# IOT_Gas.net
KiCad netlist of a schematic drawn in Altium Designer
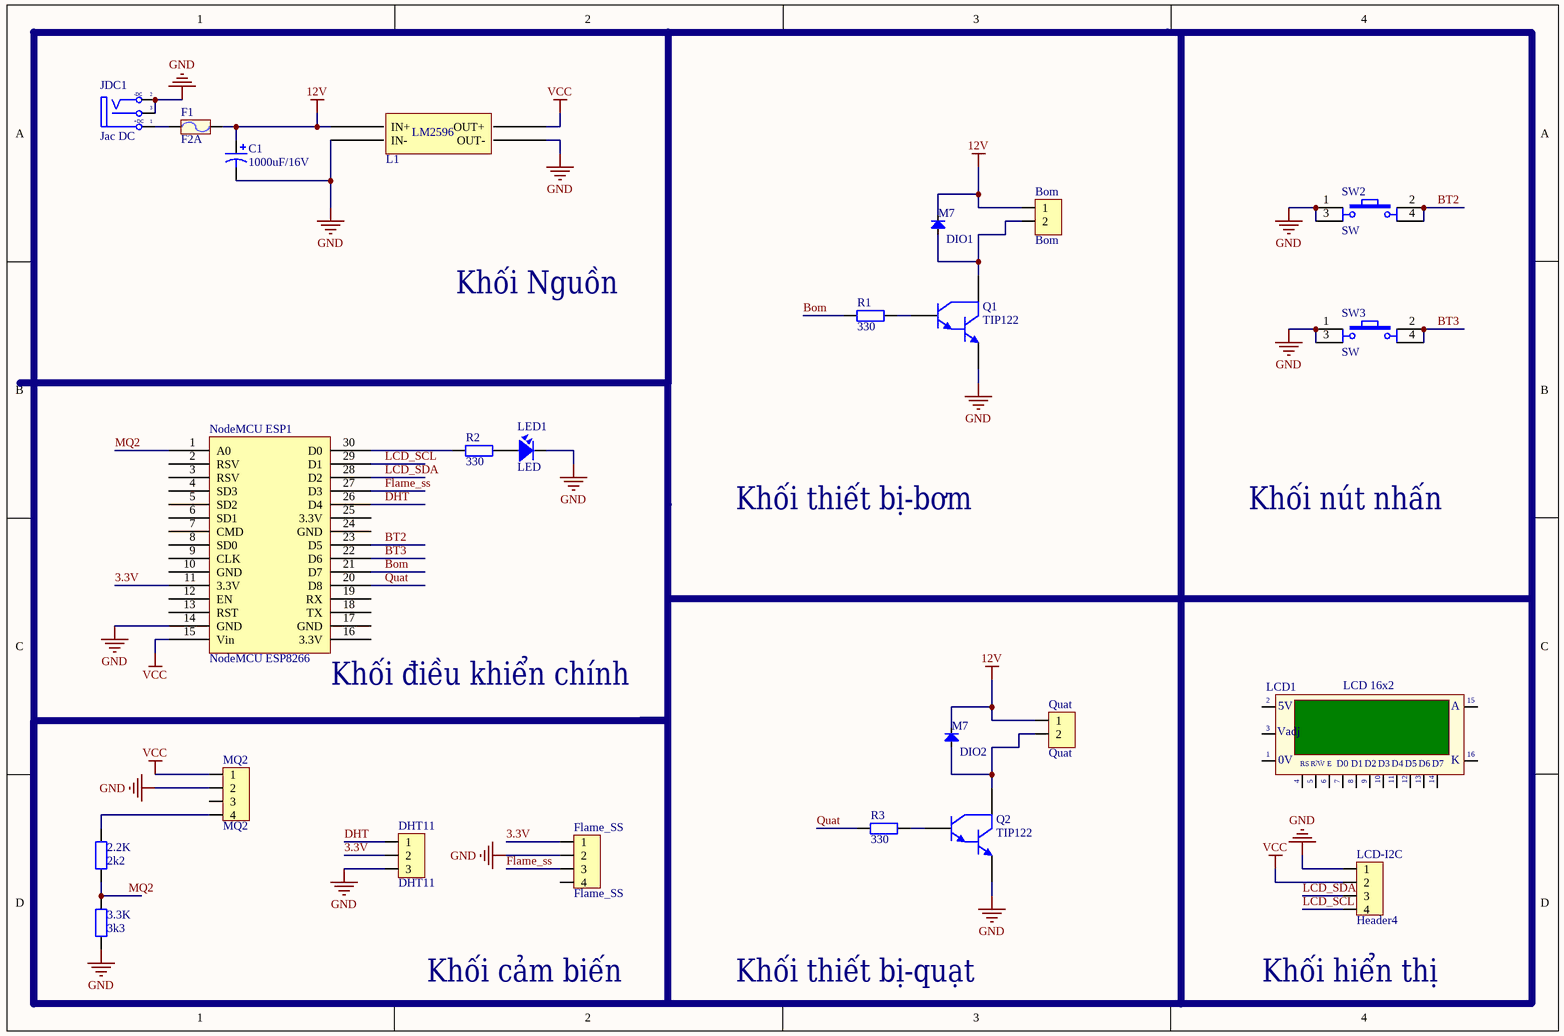
[diagram p0: IOT_Gas.SchDoc]

(export (version "E")
  (design (tool "Eeschema 10.0.6"))
  (components
    (comp (ref "2.2K")
      (value "2k2")
      (footprint "DIEN TRO 0805")
      (description "Resistor SMD 0805")
      (fields (field (name "PUBLISHER") "Altium Limited"))
      (libsource (lib "") (part "R0805_1"))
    )
    (comp (ref "3.3K")
      (value "3k3")
      (footprint "DIEN TRO 0805")
      (description "Resistor SMD 0805")
      (fields (field (name "PUBLISHER") "Altium Limited"))
      (libsource (lib "") (part "R0805_1"))
    )
    (comp (ref "Bom")
      (value "Bom")
      (footprint "Header2")
      (description "Header IDC, 2 x 1 Pin Vertical 2.54mm Pitch (Non-Boxed, Male)")
      (fields
        (field (name "MANUFACTURER") "Würth Elektronik eiSos GmbH")
        (field (name "PARTNO") "613002143121")
        (field (name "CREATED BY") "Karrer Zheng")
      )
      (libsource (lib "My Library") (part "Header2"))
    )
    (comp (ref "C1")
      (value "1000uF/16V")
      (footprint "C10mm")
      (description "Polarized Capacitor (Axial)")
      (fields (field (name "PUBLISHER") "Altium Limited"))
      (libsource (lib "My Library") (part "Cap Pol 12mm"))
    )
    (comp (ref "DHT11")
      (value "DHT11")
      (footprint "Header3")
      (description "Header IDC, 3 x 1 Pin Vertical 2.54mm Pitch (Non-Boxed, Male)")
      (fields
        (field (name "MANUFACTURER") "Würth Elektronik eiSos GmbH")
        (field (name "PARTNO") "613002143121")
        (field (name "CREATED BY") "Karrer Zheng")
      )
      (libsource (lib "My Library") (part "Header3"))
    )
    (comp (ref "DIO1")
      (value "M7")
      (footprint "DIO-SMD-106")
      (description "Default Diode")
      (fields (field (name "PUBLISHER") "Altium Limited"))
      (libsource (lib "My Library (1)") (part "Diode SMD"))
    )
    (comp (ref "DIO2")
      (value "M7")
      (footprint "DIO-SMD-106")
      (description "Default Diode")
      (fields (field (name "PUBLISHER") "Altium Limited"))
      (libsource (lib "My Library (1)") (part "Diode SMD"))
    )
    (comp (ref "F1")
      (value "F2A")
      (footprint "Fuse")
      (description "Fuse")
      (fields (field (name "DESIGNED BY") "VanDungEvn"))
      (libsource (lib "My Library") (part "Fuse"))
    )
    (comp (ref "Flame_SS")
      (value "Flame_SS")
      (footprint "HDR4")
      (description "Header IDC, 4 x 1 Pin Vertical 2.54mm Pitch (Non-Boxed, Male)")
      (fields
        (field (name "MANUFACTURER") "Würth Elektronik eiSos GmbH")
        (field (name "PARTNO") "613002143121")
        (field (name "CREATED BY") "Karrer Zheng")
      )
      (libsource (lib "My Library") (part "Header4"))
    )
    (comp (ref "JDC1")
      (value "Jac DC")
      (footprint "DC-IN")
      (description "Jac DC input")
      (libsource (lib "My Library") (part "DCIN"))
    )
    (comp (ref "L1")
      (value "BUCK_LM2596")
      (footprint "BUCK_LM2596")
      (libsource (lib "BUCK_LM2596_Sch") (part "BUCK_LM2596"))
    )
    (comp (ref "LCD-I2C")
      (value "Header4")
      (footprint "HDR4")
      (description "Header IDC, 4 x 1 Pin Vertical 2.54mm Pitch (Non-Boxed, Male)")
      (fields
        (field (name "MANUFACTURER") "Würth Elektronik eiSos GmbH")
        (field (name "PARTNO") "613002143121")
        (field (name "CREATED BY") "Karrer Zheng")
      )
      (libsource (lib "My Library") (part "Header4"))
    )
    (comp (ref "LCD1")
      (value "LCD 16x2")
      (footprint "LCD16X2N")
      (libsource (lib "My library altium") (part "LCD"))
    )
    (comp (ref "LED1")
      (value "LED")
      (footprint "LED-5 GRe")
      (description "LED Single colour Green and Red")
      (libsource (lib "My Library") (part "LED"))
    )
    (comp (ref "MQ2")
      (value "MQ2")
      (footprint "HDR4")
      (description "Header IDC, 4 x 1 Pin Vertical 2.54mm Pitch (Non-Boxed, Male)")
      (fields
        (field (name "MANUFACTURER") "Würth Elektronik eiSos GmbH")
        (field (name "PARTNO") "613002143121")
        (field (name "CREATED BY") "Karrer Zheng")
      )
      (libsource (lib "My Library") (part "Header4"))
    )
    (comp (ref "NodeMCU ESP1")
      (value "NodeMCU ESP8266")
      (footprint "NodeMCU ESP8266")
      (libsource (lib "Phieu_Du") (part "NodeMCU ESP8266"))
    )
    (comp (ref "Q1")
      (value "TIP122")
      (footprint "QTO-220")
      (description "Darlington Silicon Power NPN Transistor, 8 Amp, 100 Volts and 65 Watts")
      (libsource (lib "My Library (1)") (part "TIP122"))
    )
    (comp (ref "Q2")
      (value "TIP122")
      (footprint "QTO-220")
      (description "Darlington Silicon Power NPN Transistor, 8 Amp, 100 Volts and 65 Watts")
      (libsource (lib "My Library (1)") (part "TIP122"))
    )
    (comp (ref "Quat")
      (value "Quat")
      (footprint "Header2")
      (description "Header IDC, 2 x 1 Pin Vertical 2.54mm Pitch (Non-Boxed, Male)")
      (fields
        (field (name "MANUFACTURER") "Würth Elektronik eiSos GmbH")
        (field (name "PARTNO") "613002143121")
        (field (name "CREATED BY") "Karrer Zheng")
      )
      (libsource (lib "My Library") (part "Header2"))
    )
    (comp (ref "R1")
      (value "330")
      (footprint "DIEN TRO 0805")
      (description "Resistor SMD 0805")
      (fields (field (name "PUBLISHER") "Altium Limited"))
      (libsource (lib "My Library (1)") (part "R0805"))
    )
    (comp (ref "R2")
      (value "330")
      (footprint "DIEN TRO 0805")
      (description "Resistor SMD 0805")
      (fields (field (name "PUBLISHER") "Altium Limited"))
      (libsource (lib "My Library (1)") (part "R0805"))
    )
    (comp (ref "R3")
      (value "330")
      (footprint "DIEN TRO 0805")
      (description "Resistor SMD 0805")
      (fields (field (name "PUBLISHER") "Altium Limited"))
      (libsource (lib "My Library (1)") (part "R0805"))
    )
    (comp (ref "SW2")
      (value "SW")
      (footprint "SW4")
      (description "Switch button 4 pin")
      (libsource (lib "My Library (1)") (part "SW4"))
    )
    (comp (ref "SW3")
      (value "SW")
      (footprint "SW4")
      (description "Switch button 4 pin")
      (libsource (lib "My Library (1)") (part "SW4"))
    )
  )
  (nets
    (net (code "1") (name "/3.3V") (class "Default")
      (node (ref "DHT11") (pin "2") (pinfunction "2_2") (pintype "passive"))
      (node (ref "Flame_SS") (pin "1") (pinfunction "1_1") (pintype "passive"))
      (node (ref "NodeMCU ESP1") (pin "11") (pinfunction "3.3V_11") (pintype "passive"))
    )
    (net (code "2") (name "/BT2") (class "Default")
      (node (ref "NodeMCU ESP1") (pin "23") (pinfunction "D5_23") (pintype "passive"))
      (node (ref "SW2") (pin "2") (pintype "passive"))
      (node (ref "SW2") (pin "4") (pintype "passive"))
    )
    (net (code "3") (name "/BT3") (class "Default")
      (node (ref "NodeMCU ESP1") (pin "22") (pinfunction "D6_22") (pintype "passive"))
      (node (ref "SW3") (pin "2") (pintype "passive"))
      (node (ref "SW3") (pin "4") (pintype "passive"))
    )
    (net (code "4") (name "/Bom") (class "Default")
      (node (ref "NodeMCU ESP1") (pin "21") (pinfunction "D7_21") (pintype "passive"))
      (node (ref "R1") (pin "2") (pinfunction "2_2") (pintype "passive"))
    )
    (net (code "5") (name "/DHT") (class "Default")
      (node (ref "DHT11") (pin "1") (pinfunction "1_1") (pintype "passive"))
      (node (ref "NodeMCU ESP1") (pin "26") (pinfunction "D4_26") (pintype "passive"))
    )
    (net (code "6") (name "/Flame_ss") (class "Default")
      (node (ref "Flame_SS") (pin "3") (pinfunction "3_3") (pintype "passive"))
      (node (ref "NodeMCU ESP1") (pin "27") (pinfunction "D3_27") (pintype "passive"))
    )
    (net (code "7") (name "/LCD_SCL") (class "Default")
      (node (ref "LCD-I2C") (pin "4") (pinfunction "4_4") (pintype "passive"))
      (node (ref "NodeMCU ESP1") (pin "29") (pinfunction "D1_29") (pintype "passive"))
    )
    (net (code "8") (name "/LCD_SDA") (class "Default")
      (node (ref "LCD-I2C") (pin "3") (pinfunction "3_3") (pintype "passive"))
      (node (ref "NodeMCU ESP1") (pin "28") (pinfunction "D2_28") (pintype "passive"))
    )
    (net (code "9") (name "/MQ2") (class "Default")
      (node (ref "2.2K") (pin "2") (pinfunction "2_2") (pintype "passive"))
      (node (ref "3.3K") (pin "1") (pinfunction "1_1") (pintype "passive"))
      (node (ref "NodeMCU ESP1") (pin "1") (pinfunction "A0_1") (pintype "passive"))
    )
    (net (code "10") (name "/Quat") (class "Default")
      (node (ref "NodeMCU ESP1") (pin "20") (pinfunction "D8_20") (pintype "passive"))
      (node (ref "R3") (pin "2") (pinfunction "2_2") (pintype "passive"))
    )
    (net (code "11") (name "12V") (class "Default")
      (node (ref "Bom") (pin "1") (pinfunction "1_1") (pintype "passive"))
      (node (ref "C1") (pin "1") (pinfunction "1_1") (pintype "passive"))
      (node (ref "DIO1") (pin "2") (pinfunction "K_2") (pintype "passive"))
      (node (ref "DIO2") (pin "2") (pinfunction "K_2") (pintype "passive"))
      (node (ref "F1") (pin "2") (pinfunction "2_2") (pintype "passive"))
      (node (ref "L1") (pin "1") (pinfunction "IN+_1") (pintype "passive"))
      (node (ref "Quat") (pin "1") (pinfunction "1_1") (pintype "passive"))
    )
    (net (code "12") (name "GND") (class "Default")
      (node (ref "3.3K") (pin "2") (pinfunction "2_2") (pintype "passive"))
      (node (ref "C1") (pin "2") (pinfunction "2_2") (pintype "passive"))
      (node (ref "DHT11") (pin "3") (pinfunction "3_3") (pintype "passive"))
      (node (ref "Flame_SS") (pin "2") (pinfunction "2_2") (pintype "passive"))
      (node (ref "JDC1") (pin "2") (pinfunction "TN_2") (pintype "passive"))
      (node (ref "JDC1") (pin "3") (pinfunction "S_3") (pintype "power_in"))
      (node (ref "L1") (pin "2") (pinfunction "IN-_2") (pintype "passive"))
      (node (ref "L1") (pin "3") (pinfunction "OUT-_3") (pintype "passive"))
      (node (ref "LCD-I2C") (pin "1") (pinfunction "1_1") (pintype "passive"))
      (node (ref "LED1") (pin "2") (pinfunction "2_2") (pintype "passive"))
      (node (ref "MQ2") (pin "2") (pinfunction "2_2") (pintype "passive"))
      (node (ref "NodeMCU ESP1") (pin "14") (pinfunction "GND_14") (pintype "passive"))
      (node (ref "Q1") (pin "3") (pinfunction "E_3") (pintype "passive"))
      (node (ref "Q2") (pin "3") (pinfunction "E_3") (pintype "passive"))
      (node (ref "SW2") (pin "1") (pintype "passive"))
      (node (ref "SW2") (pin "3") (pintype "passive"))
      (node (ref "SW3") (pin "1") (pintype "passive"))
      (node (ref "SW3") (pin "3") (pintype "passive"))
    )
    (net (code "13") (name "Net-(2.2K-Pad1)") (class "Default")
      (node (ref "2.2K") (pin "1") (pinfunction "1_1") (pintype "passive"))
      (node (ref "MQ2") (pin "4") (pinfunction "4_4") (pintype "passive"))
    )
    (net (code "14") (name "Net-(DIO1-A)") (class "Default")
      (node (ref "Bom") (pin "2") (pinfunction "2_2") (pintype "passive"))
      (node (ref "DIO1") (pin "1") (pinfunction "A_1") (pintype "passive"))
      (node (ref "Q1") (pin "2") (pinfunction "C_2") (pintype "passive"))
    )
    (net (code "15") (name "Net-(DIO2-A)") (class "Default")
      (node (ref "DIO2") (pin "1") (pinfunction "A_1") (pintype "passive"))
      (node (ref "Q2") (pin "2") (pinfunction "C_2") (pintype "passive"))
      (node (ref "Quat") (pin "2") (pinfunction "2_2") (pintype "passive"))
    )
    (net (code "16") (name "Net-(JDC1-T)") (class "Default")
      (node (ref "F1") (pin "1") (pinfunction "1_1") (pintype "passive"))
      (node (ref "JDC1") (pin "1") (pinfunction "T_1") (pintype "passive"))
    )
    (net (code "17") (name "Net-(LED1-Pad1)") (class "Default")
      (node (ref "LED1") (pin "1") (pinfunction "1_1") (pintype "passive"))
      (node (ref "R2") (pin "1") (pinfunction "1_1") (pintype "passive"))
    )
    (net (code "18") (name "Net-(NodeMCU ESP1-D0)") (class "Default")
      (node (ref "NodeMCU ESP1") (pin "30") (pinfunction "D0_30") (pintype "passive"))
      (node (ref "R2") (pin "2") (pinfunction "2_2") (pintype "passive"))
    )
    (net (code "19") (name "Net-(Q1-B)") (class "Default")
      (node (ref "Q1") (pin "1") (pinfunction "B_1") (pintype "passive"))
      (node (ref "R1") (pin "1") (pinfunction "1_1") (pintype "passive"))
    )
    (net (code "20") (name "Net-(Q2-B)") (class "Default")
      (node (ref "Q2") (pin "1") (pinfunction "B_1") (pintype "passive"))
      (node (ref "R3") (pin "1") (pinfunction "1_1") (pintype "passive"))
    )
    (net (code "21") (name "VCC") (class "Default")
      (node (ref "L1") (pin "4") (pinfunction "OUT+_4") (pintype "passive"))
      (node (ref "LCD-I2C") (pin "2") (pinfunction "2_2") (pintype "passive"))
      (node (ref "MQ2") (pin "1") (pinfunction "1_1") (pintype "passive"))
      (node (ref "NodeMCU ESP1") (pin "15") (pinfunction "Vin_15") (pintype "passive"))
    )
    (net (code "22") (name "unconnected-(Flame_SS-Pad4)") (class "Default")
      (node (ref "Flame_SS") (pin "4") (pinfunction "4_4") (pintype "passive"))
    )
    (net (code "23") (name "unconnected-(LCD1-A-Pad15)") (class "Default")
      (node (ref "LCD1") (pin "15") (pinfunction "A_15") (pintype "passive"))
    )
    (net (code "24") (name "unconnected-(LCD1-D0-Pad7)") (class "Default")
      (node (ref "LCD1") (pin "7") (pinfunction "D0_7") (pintype "passive"))
    )
    (net (code "25") (name "unconnected-(LCD1-D1-Pad8)") (class "Default")
      (node (ref "LCD1") (pin "8") (pinfunction "D1_8") (pintype "passive"))
    )
    (net (code "26") (name "unconnected-(LCD1-D2-Pad9)") (class "Default")
      (node (ref "LCD1") (pin "9") (pinfunction "D2_9") (pintype "passive"))
    )
    (net (code "27") (name "unconnected-(LCD1-D3-Pad10)") (class "Default")
      (node (ref "LCD1") (pin "10") (pinfunction "D3_10") (pintype "passive"))
    )
    (net (code "28") (name "unconnected-(LCD1-D4-Pad11)") (class "Default")
      (node (ref "LCD1") (pin "11") (pinfunction "D4_11") (pintype "passive"))
    )
    (net (code "29") (name "unconnected-(LCD1-D5-Pad12)") (class "Default")
      (node (ref "LCD1") (pin "12") (pinfunction "D5_12") (pintype "passive"))
    )
    (net (code "30") (name "unconnected-(LCD1-D6-Pad13)") (class "Default")
      (node (ref "LCD1") (pin "13") (pinfunction "D6_13") (pintype "passive"))
    )
    (net (code "31") (name "unconnected-(LCD1-D7-Pad14)") (class "Default")
      (node (ref "LCD1") (pin "14") (pinfunction "D7_14") (pintype "passive"))
    )
    (net (code "32") (name "unconnected-(LCD1-GND-Pad1)") (class "Default")
      (node (ref "LCD1") (pin "1") (pinfunction "GND_1") (pintype "passive"))
    )
    (net (code "33") (name "unconnected-(LCD1-K-Pad16)") (class "Default")
      (node (ref "LCD1") (pin "16") (pinfunction "K_16") (pintype "passive"))
    )
    (net (code "34") (name "unconnected-(LCD1-RS-Pad4)") (class "Default")
      (node (ref "LCD1") (pin "4") (pinfunction "RS_4") (pintype "passive"))
    )
    (net (code "35") (name "unconnected-(LCD1-R{slash}~{W}-Pad5)") (class "Default")
      (node (ref "LCD1") (pin "5") (pinfunction "R/~{W}_5") (pintype "passive"))
    )
    (net (code "36") (name "unconnected-(LCD1-VAdj-Pad3)") (class "Default")
      (node (ref "LCD1") (pin "3") (pinfunction "VAdj_3") (pintype "passive"))
    )
    (net (code "37") (name "unconnected-(LCD1-VDD-Pad2)") (class "Default")
      (node (ref "LCD1") (pin "2") (pinfunction "VDD_2") (pintype "passive"))
    )
    (net (code "38") (name "unconnected-(LCD1-~{EN}-Pad6)") (class "Default")
      (node (ref "LCD1") (pin "6") (pinfunction "~{EN}_6") (pintype "passive"))
    )
    (net (code "39") (name "unconnected-(MQ2-Pad3)") (class "Default")
      (node (ref "MQ2") (pin "3") (pinfunction "3_3") (pintype "passive"))
    )
    (net (code "40") (name "unconnected-(NodeMCU ESP1-3.3V-Pad16)") (class "Default")
      (node (ref "NodeMCU ESP1") (pin "16") (pinfunction "3.3V_16") (pintype "passive"))
    )
    (net (code "41") (name "unconnected-(NodeMCU ESP1-3.3V-Pad25)") (class "Default")
      (node (ref "NodeMCU ESP1") (pin "25") (pinfunction "3.3V_25") (pintype "passive"))
    )
    (net (code "42") (name "unconnected-(NodeMCU ESP1-CLK-Pad9)") (class "Default")
      (node (ref "NodeMCU ESP1") (pin "9") (pinfunction "CLK_9") (pintype "passive"))
    )
    (net (code "43") (name "unconnected-(NodeMCU ESP1-CMD-Pad7)") (class "Default")
      (node (ref "NodeMCU ESP1") (pin "7") (pinfunction "CMD_7") (pintype "passive"))
    )
    (net (code "44") (name "unconnected-(NodeMCU ESP1-EN-Pad12)") (class "Default")
      (node (ref "NodeMCU ESP1") (pin "12") (pinfunction "EN_12") (pintype "passive"))
    )
    (net (code "45") (name "unconnected-(NodeMCU ESP1-GND-Pad10)") (class "Default")
      (node (ref "NodeMCU ESP1") (pin "10") (pinfunction "GND_10") (pintype "passive"))
    )
    (net (code "46") (name "unconnected-(NodeMCU ESP1-GND-Pad17)") (class "Default")
      (node (ref "NodeMCU ESP1") (pin "17") (pinfunction "GND_17") (pintype "passive"))
    )
    (net (code "47") (name "unconnected-(NodeMCU ESP1-GND-Pad24)") (class "Default")
      (node (ref "NodeMCU ESP1") (pin "24") (pinfunction "GND_24") (pintype "passive"))
    )
    (net (code "48") (name "unconnected-(NodeMCU ESP1-RST-Pad13)") (class "Default")
      (node (ref "NodeMCU ESP1") (pin "13") (pinfunction "RST_13") (pintype "passive"))
    )
    (net (code "49") (name "unconnected-(NodeMCU ESP1-RSV-Pad2)") (class "Default")
      (node (ref "NodeMCU ESP1") (pin "2") (pinfunction "RSV_2") (pintype "passive"))
    )
    (net (code "50") (name "unconnected-(NodeMCU ESP1-RSV-Pad3)") (class "Default")
      (node (ref "NodeMCU ESP1") (pin "3") (pinfunction "RSV_3") (pintype "passive"))
    )
    (net (code "51") (name "unconnected-(NodeMCU ESP1-RX-Pad19)") (class "Default")
      (node (ref "NodeMCU ESP1") (pin "19") (pinfunction "RX_19") (pintype "passive"))
    )
    (net (code "52") (name "unconnected-(NodeMCU ESP1-SD0-Pad8)") (class "Default")
      (node (ref "NodeMCU ESP1") (pin "8") (pinfunction "SD0_8") (pintype "passive"))
    )
    (net (code "53") (name "unconnected-(NodeMCU ESP1-SD1-Pad6)") (class "Default")
      (node (ref "NodeMCU ESP1") (pin "6") (pinfunction "SD1_6") (pintype "passive"))
    )
    (net (code "54") (name "unconnected-(NodeMCU ESP1-SD2-Pad5)") (class "Default")
      (node (ref "NodeMCU ESP1") (pin "5") (pinfunction "SD2_5") (pintype "passive"))
    )
    (net (code "55") (name "unconnected-(NodeMCU ESP1-SD3-Pad4)") (class "Default")
      (node (ref "NodeMCU ESP1") (pin "4") (pinfunction "SD3_4") (pintype "passive"))
    )
    (net (code "56") (name "unconnected-(NodeMCU ESP1-TX-Pad18)") (class "Default")
      (node (ref "NodeMCU ESP1") (pin "18") (pinfunction "TX_18") (pintype "passive"))
    )
  )
)
